# ElectroSketch.net
KiCad netlist of a schematic drawn in Altium Designer
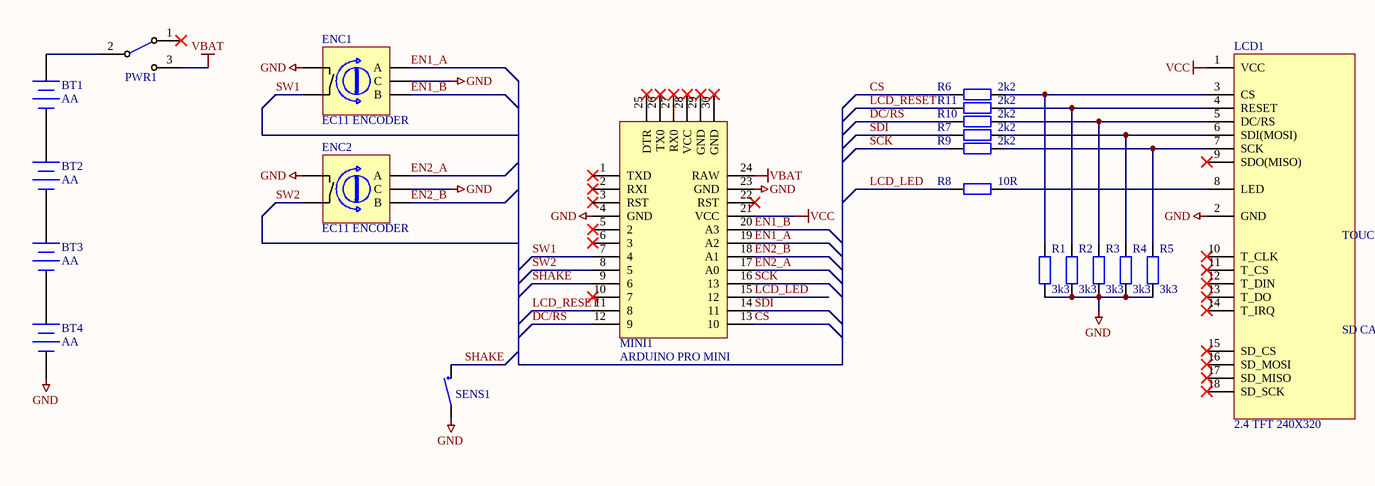
[diagram p0: ElectroSketch.SchDoc]

(export (version "E")
  (design (tool "Eeschema 10.0.6"))
  (components
    (comp (ref "BT1")
      (value "AA")
      (footprint "AA HOLDER")
      (description "Multicell Battery")
      (fields (field (name "PUBLISHER") "Altium Limited"))
      (libsource (lib "Miscellaneous Devices") (part "Battery"))
    )
    (comp (ref "BT2")
      (value "AA")
      (footprint "AA HOLDER")
      (description "Multicell Battery")
      (fields (field (name "PUBLISHER") "Altium Limited"))
      (libsource (lib "Miscellaneous Devices") (part "Battery"))
    )
    (comp (ref "BT3")
      (value "AA")
      (footprint "AA HOLDER")
      (description "Multicell Battery")
      (fields (field (name "PUBLISHER") "Altium Limited"))
      (libsource (lib "Miscellaneous Devices") (part "Battery"))
    )
    (comp (ref "BT4")
      (value "AA")
      (footprint "AA HOLDER")
      (description "Multicell Battery")
      (fields (field (name "PUBLISHER") "Altium Limited"))
      (libsource (lib "Miscellaneous Devices") (part "Battery"))
    )
    (comp (ref "ENC1")
      (value "EC11 ENCODER")
      (footprint "newpcb:EC11 ENCODER")
      (description "EC11 ROTARY ENCODER WITH PUSH BUTTON")
      (libsource (lib "EletroSketch") (part "EC11 ENCODER"))
    )
    (comp (ref "ENC2")
      (value "EC11 ENCODER")
      (footprint "newpcb:EC11 ENCODER")
      (description "EC11 ROTARY ENCODER WITH PUSH BUTTON")
      (libsource (lib "EletroSketch") (part "EC11 ENCODER"))
    )
    (comp (ref "LCD1")
      (value "2.4 TFT 240X320")
      (footprint "newpcb:2.4\" TFT LCD")
      (libsource (lib "EletroSketch") (part "2.4 TFT 240X320"))
    )
    (comp (ref "MINI1")
      (value "ARDUINO PRO MINI")
      (footprint "ARDUINO PRO MINI")
      (libsource (lib "EletroSketch") (part "ARDUINO PRO MINI"))
    )
    (comp (ref "PWR1")
      (value "SS12D00G3")
      (footprint "SS12D00G3")
      (description "SS12D00G3 Toggle Switch")
      (libsource (lib "Schlib1") (part "SS12D00G3 Toggle Switch"))
    )
    (comp (ref "R1")
      (value "3k3")
      (footprint "newpcb:RESISTOR 0.400\"")
      (description "RESISITOR THROUGH HOLE 1/4W")
      (libsource (lib "FavoritesLibrary") (part "SYM-iaxfckaaxq3jb0c9euu5-1"))
    )
    (comp (ref "R2")
      (value "3k3")
      (footprint "newpcb:RESISTOR 0.400\"")
      (description "RESISITOR THROUGH HOLE 1/4W")
      (libsource (lib "FavoritesLibrary") (part "SYM-iaxfckaaxq3jb0c9euu5-1"))
    )
    (comp (ref "R3")
      (value "3k3")
      (footprint "newpcb:RESISTOR 0.400\"")
      (description "RESISITOR THROUGH HOLE 1/4W")
      (libsource (lib "FavoritesLibrary") (part "SYM-iaxfckaaxq3jb0c9euu5-1"))
    )
    (comp (ref "R4")
      (value "3k3")
      (footprint "newpcb:RESISTOR 0.400\"")
      (description "RESISITOR THROUGH HOLE 1/4W")
      (libsource (lib "FavoritesLibrary") (part "SYM-iaxfckaaxq3jb0c9euu5-1"))
    )
    (comp (ref "R5")
      (value "3k3")
      (footprint "newpcb:RESISTOR 0.400\"")
      (description "RESISITOR THROUGH HOLE 1/4W")
      (libsource (lib "FavoritesLibrary") (part "SYM-iaxfckaaxq3jb0c9euu5-1"))
    )
    (comp (ref "R6")
      (value "2k2")
      (footprint "newpcb:RESISTOR 0.400\"")
      (description "RESISITOR THROUGH HOLE 1/4W")
      (libsource (lib "") (part "SYM-iaxfckaaxq3jb0c9euu5-1_1"))
    )
    (comp (ref "R7")
      (value "2k2")
      (footprint "newpcb:RESISTOR 0.400\"")
      (description "RESISITOR THROUGH HOLE 1/4W")
      (libsource (lib "") (part "SYM-iaxfckaaxq3jb0c9euu5-1_1"))
    )
    (comp (ref "R8")
      (value "10R")
      (footprint "newpcb:RESISTOR 0.400\"")
      (description "RESISITOR THROUGH HOLE 1/4W")
      (libsource (lib "") (part "SYM-iaxfckaaxq3jb0c9euu5-1_2"))
    )
    (comp (ref "R9")
      (value "2k2")
      (footprint "newpcb:RESISTOR 0.400\"")
      (description "RESISITOR THROUGH HOLE 1/4W")
      (libsource (lib "") (part "SYM-iaxfckaaxq3jb0c9euu5-1_1"))
    )
    (comp (ref "R10")
      (value "2k2")
      (footprint "newpcb:RESISTOR 0.400\"")
      (description "RESISITOR THROUGH HOLE 1/4W")
      (libsource (lib "") (part "SYM-iaxfckaaxq3jb0c9euu5-1_1"))
    )
    (comp (ref "R11")
      (value "2k2")
      (footprint "newpcb:RESISTOR 0.400\"")
      (description "RESISITOR THROUGH HOLE 1/4W")
      (libsource (lib "") (part "SYM-iaxfckaaxq3jb0c9euu5-1_1"))
    )
    (comp (ref "SENS1")
      (value "SHAKE SENSOR")
      (footprint "SHAKE SENSOR")
      (fields (field (name "PUBLISHER") "Altium Limited"))
      (libsource (lib "EletroSketch") (part "SHAKE SENSOR"))
    )
  )
  (nets
    (net (code "1") (name "/CS") (class "Default")
      (node (ref "MINI1") (pin "13") (pinfunction "10_13") (pintype "passive"))
      (node (ref "R6") (pin "1") (pinfunction "1_1") (pintype "passive"))
    )
    (net (code "2") (name "/DC{slash}RS") (class "Default")
      (node (ref "MINI1") (pin "12") (pinfunction "9_12") (pintype "passive"))
      (node (ref "R10") (pin "1") (pinfunction "1_1") (pintype "passive"))
    )
    (net (code "3") (name "/EN1_A") (class "Default")
      (node (ref "ENC1") (pin "1") (pinfunction "A_1") (pintype "passive"))
      (node (ref "MINI1") (pin "19") (pinfunction "A2_19") (pintype "passive"))
    )
    (net (code "4") (name "/EN1_B") (class "Default")
      (node (ref "ENC1") (pin "3") (pinfunction "B_3") (pintype "passive"))
      (node (ref "MINI1") (pin "20") (pinfunction "A3_20") (pintype "passive"))
    )
    (net (code "5") (name "/EN2_A") (class "Default")
      (node (ref "ENC2") (pin "1") (pinfunction "A_1") (pintype "passive"))
      (node (ref "MINI1") (pin "17") (pinfunction "A0_17") (pintype "passive"))
    )
    (net (code "6") (name "/EN2_B") (class "Default")
      (node (ref "ENC2") (pin "3") (pinfunction "B_3") (pintype "passive"))
      (node (ref "MINI1") (pin "18") (pinfunction "A1_18") (pintype "passive"))
    )
    (net (code "7") (name "/LCD_LED") (class "Default")
      (node (ref "MINI1") (pin "15") (pinfunction "12_15") (pintype "passive"))
      (node (ref "R8") (pin "2") (pinfunction "2_2") (pintype "passive"))
    )
    (net (code "8") (name "/LCD_RESET") (class "Default")
      (node (ref "MINI1") (pin "11") (pinfunction "8_11") (pintype "passive"))
      (node (ref "R11") (pin "1") (pinfunction "1_1") (pintype "passive"))
    )
    (net (code "9") (name "/SCK") (class "Default")
      (node (ref "MINI1") (pin "16") (pinfunction "13_16") (pintype "passive"))
      (node (ref "R9") (pin "1") (pinfunction "1_1") (pintype "passive"))
    )
    (net (code "10") (name "/SDI") (class "Default")
      (node (ref "MINI1") (pin "14") (pinfunction "11_14") (pintype "passive"))
      (node (ref "R7") (pin "1") (pinfunction "1_1") (pintype "passive"))
    )
    (net (code "11") (name "/SHAKE") (class "Default")
      (node (ref "MINI1") (pin "9") (pinfunction "6_9") (pintype "passive"))
      (node (ref "SENS1") (pin "2") (pinfunction "2_2") (pintype "passive"))
    )
    (net (code "12") (name "/SW1") (class "Default")
      (node (ref "ENC1") (pin "5") (pinfunction "SW_1_5") (pintype "passive"))
      (node (ref "MINI1") (pin "7") (pinfunction "4_7") (pintype "passive"))
    )
    (net (code "13") (name "/SW2") (class "Default")
      (node (ref "ENC2") (pin "5") (pinfunction "SW_1_5") (pintype "passive"))
      (node (ref "MINI1") (pin "8") (pinfunction "5_8") (pintype "passive"))
    )
    (net (code "14") (name "GND") (class "Default")
      (node (ref "BT4") (pin "2") (pinfunction "-_2") (pintype "passive"))
      (node (ref "ENC1") (pin "2") (pinfunction "C_2") (pintype "passive"))
      (node (ref "ENC1") (pin "4") (pinfunction "SW_0_4") (pintype "passive"))
      (node (ref "ENC2") (pin "2") (pinfunction "C_2") (pintype "passive"))
      (node (ref "ENC2") (pin "4") (pinfunction "SW_0_4") (pintype "passive"))
      (node (ref "LCD1") (pin "2") (pinfunction "GND_2") (pintype "passive"))
      (node (ref "MINI1") (pin "23") (pinfunction "GND_23") (pintype "passive"))
      (node (ref "MINI1") (pin "4") (pinfunction "GND_4") (pintype "passive"))
      (node (ref "R1") (pin "1") (pinfunction "1_1") (pintype "passive"))
      (node (ref "R2") (pin "1") (pinfunction "1_1") (pintype "passive"))
      (node (ref "R3") (pin "1") (pinfunction "1_1") (pintype "passive"))
      (node (ref "R4") (pin "1") (pinfunction "1_1") (pintype "passive"))
      (node (ref "R5") (pin "1") (pinfunction "1_1") (pintype "passive"))
      (node (ref "SENS1") (pin "1") (pinfunction "1_1") (pintype "passive"))
    )
    (net (code "15") (name "Net-(BT1-+)") (class "Default")
      (node (ref "BT1") (pin "1") (pinfunction "+_1") (pintype "passive"))
      (node (ref "PWR1") (pin "2") (pinfunction "2_2") (pintype "passive"))
    )
    (net (code "16") (name "Net-(BT1--)") (class "Default")
      (node (ref "BT1") (pin "2") (pinfunction "-_2") (pintype "passive"))
      (node (ref "BT2") (pin "1") (pinfunction "+_1") (pintype "passive"))
    )
    (net (code "17") (name "Net-(BT2--)") (class "Default")
      (node (ref "BT2") (pin "2") (pinfunction "-_2") (pintype "passive"))
      (node (ref "BT3") (pin "1") (pinfunction "+_1") (pintype "passive"))
    )
    (net (code "18") (name "Net-(BT3--)") (class "Default")
      (node (ref "BT3") (pin "2") (pinfunction "-_2") (pintype "passive"))
      (node (ref "BT4") (pin "1") (pinfunction "+_1") (pintype "passive"))
    )
    (net (code "19") (name "Net-(LCD1-CS)") (class "Default")
      (node (ref "LCD1") (pin "3") (pinfunction "CS_3") (pintype "passive"))
      (node (ref "R1") (pin "2") (pinfunction "2_2") (pintype "passive"))
      (node (ref "R6") (pin "2") (pinfunction "2_2") (pintype "passive"))
    )
    (net (code "20") (name "Net-(LCD1-DC{slash}RS)") (class "Default")
      (node (ref "LCD1") (pin "5") (pinfunction "DC/RS_5") (pintype "passive"))
      (node (ref "R10") (pin "2") (pinfunction "2_2") (pintype "passive"))
      (node (ref "R3") (pin "2") (pinfunction "2_2") (pintype "passive"))
    )
    (net (code "21") (name "Net-(LCD1-LED)") (class "Default")
      (node (ref "LCD1") (pin "8") (pinfunction "LED_8") (pintype "passive"))
      (node (ref "R8") (pin "1") (pinfunction "1_1") (pintype "passive"))
    )
    (net (code "22") (name "Net-(LCD1-RESET)") (class "Default")
      (node (ref "LCD1") (pin "4") (pinfunction "RESET_4") (pintype "passive"))
      (node (ref "R11") (pin "2") (pinfunction "2_2") (pintype "passive"))
      (node (ref "R2") (pin "2") (pinfunction "2_2") (pintype "passive"))
    )
    (net (code "23") (name "Net-(LCD1-SCK)") (class "Default")
      (node (ref "LCD1") (pin "7") (pinfunction "SCK_7") (pintype "passive"))
      (node (ref "R5") (pin "2") (pinfunction "2_2") (pintype "passive"))
      (node (ref "R9") (pin "2") (pinfunction "2_2") (pintype "passive"))
    )
    (net (code "24") (name "Net-(LCD1-SDI(MOSI))") (class "Default")
      (node (ref "LCD1") (pin "6") (pinfunction "SDI(MOSI)_6") (pintype "passive"))
      (node (ref "R4") (pin "2") (pinfunction "2_2") (pintype "passive"))
      (node (ref "R7") (pin "2") (pinfunction "2_2") (pintype "passive"))
    )
    (net (code "25") (name "VBAT") (class "Default")
      (node (ref "MINI1") (pin "24") (pinfunction "RAW_24") (pintype "passive"))
      (node (ref "PWR1") (pin "3") (pinfunction "3_3") (pintype "passive"))
    )
    (net (code "26") (name "VCC") (class "Default")
      (node (ref "LCD1") (pin "1") (pinfunction "VCC_1") (pintype "passive"))
      (node (ref "MINI1") (pin "21") (pinfunction "VCC_21") (pintype "passive"))
    )
    (net (code "27") (name "unconnected-(LCD1-SDO(MISO)-Pad9)") (class "Default")
      (node (ref "LCD1") (pin "9") (pinfunction "SDO(MISO)_9") (pintype "passive+no_connect"))
    )
    (net (code "28") (name "unconnected-(LCD1-SD_CS-Pad15)") (class "Default")
      (node (ref "LCD1") (pin "15") (pinfunction "SD_CS_15") (pintype "passive+no_connect"))
    )
    (net (code "29") (name "unconnected-(LCD1-SD_MISO-Pad17)") (class "Default")
      (node (ref "LCD1") (pin "17") (pinfunction "SD_MISO_17") (pintype "passive+no_connect"))
    )
    (net (code "30") (name "unconnected-(LCD1-SD_MOSI-Pad16)") (class "Default")
      (node (ref "LCD1") (pin "16") (pinfunction "SD_MOSI_16") (pintype "passive+no_connect"))
    )
    (net (code "31") (name "unconnected-(LCD1-SD_SCK-Pad18)") (class "Default")
      (node (ref "LCD1") (pin "18") (pinfunction "SD_SCK_18") (pintype "passive+no_connect"))
    )
    (net (code "32") (name "unconnected-(LCD1-T_CLK-Pad10)") (class "Default")
      (node (ref "LCD1") (pin "10") (pinfunction "T_CLK_10") (pintype "passive+no_connect"))
    )
    (net (code "33") (name "unconnected-(LCD1-T_CS-Pad11)") (class "Default")
      (node (ref "LCD1") (pin "11") (pinfunction "T_CS_11") (pintype "passive+no_connect"))
    )
    (net (code "34") (name "unconnected-(LCD1-T_DIN-Pad12)") (class "Default")
      (node (ref "LCD1") (pin "12") (pinfunction "T_DIN_12") (pintype "passive+no_connect"))
    )
    (net (code "35") (name "unconnected-(LCD1-T_DO-Pad13)") (class "Default")
      (node (ref "LCD1") (pin "13") (pinfunction "T_DO_13") (pintype "passive+no_connect"))
    )
    (net (code "36") (name "unconnected-(LCD1-T_IRQ-Pad14)") (class "Default")
      (node (ref "LCD1") (pin "14") (pinfunction "T_IRQ_14") (pintype "passive+no_connect"))
    )
    (net (code "37") (name "unconnected-(MINI1-2-Pad5)") (class "Default")
      (node (ref "MINI1") (pin "5") (pinfunction "2_5") (pintype "passive+no_connect"))
    )
    (net (code "38") (name "unconnected-(MINI1-3-Pad6)") (class "Default")
      (node (ref "MINI1") (pin "6") (pinfunction "3_6") (pintype "passive+no_connect"))
    )
    (net (code "39") (name "unconnected-(MINI1-7-Pad10)") (class "Default")
      (node (ref "MINI1") (pin "10") (pinfunction "7_10") (pintype "passive+no_connect"))
    )
    (net (code "40") (name "unconnected-(MINI1-DTR-Pad25)") (class "Default")
      (node (ref "MINI1") (pin "25") (pinfunction "DTR_25") (pintype "passive+no_connect"))
    )
    (net (code "41") (name "unconnected-(MINI1-GND-Pad29)") (class "Default")
      (node (ref "MINI1") (pin "29") (pinfunction "GND_29") (pintype "passive+no_connect"))
    )
    (net (code "42") (name "unconnected-(MINI1-GND-Pad30)") (class "Default")
      (node (ref "MINI1") (pin "30") (pinfunction "GND_30") (pintype "passive+no_connect"))
    )
    (net (code "43") (name "unconnected-(MINI1-RST-Pad3)") (class "Default")
      (node (ref "MINI1") (pin "3") (pinfunction "RST_3") (pintype "passive+no_connect"))
    )
    (net (code "44") (name "unconnected-(MINI1-RST-Pad22)") (class "Default")
      (node (ref "MINI1") (pin "22") (pinfunction "RST_22") (pintype "passive+no_connect"))
    )
    (net (code "45") (name "unconnected-(MINI1-RX0-Pad27)") (class "Default")
      (node (ref "MINI1") (pin "27") (pinfunction "RX0_27") (pintype "passive+no_connect"))
    )
    (net (code "46") (name "unconnected-(MINI1-RXI-Pad2)") (class "Default")
      (node (ref "MINI1") (pin "2") (pinfunction "RXI_2") (pintype "passive+no_connect"))
    )
    (net (code "47") (name "unconnected-(MINI1-TX0-Pad26)") (class "Default")
      (node (ref "MINI1") (pin "26") (pinfunction "TX0_26") (pintype "passive+no_connect"))
    )
    (net (code "48") (name "unconnected-(MINI1-TXD-Pad1)") (class "Default")
      (node (ref "MINI1") (pin "1") (pinfunction "TXD_1") (pintype "passive+no_connect"))
    )
    (net (code "49") (name "unconnected-(MINI1-VCC-Pad28)") (class "Default")
      (node (ref "MINI1") (pin "28") (pinfunction "VCC_28") (pintype "passive+no_connect"))
    )
    (net (code "50") (name "unconnected-(PWR1-Pad1)") (class "Default")
      (node (ref "PWR1") (pin "1") (pinfunction "1_1") (pintype "passive+no_connect"))
    )
  )
)
